# V2_aktuell_StdTeile_panel_small.net
KiCad netlist of a schematic drawn in EAGLE
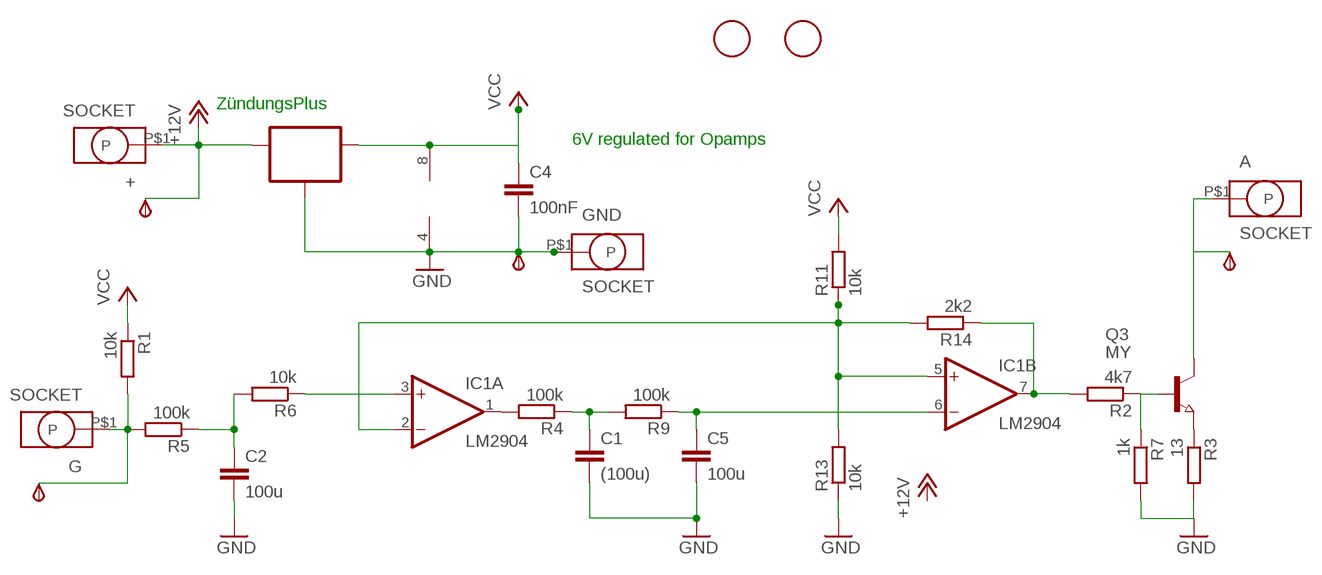
[diagram p0: schematic, sheet 1]
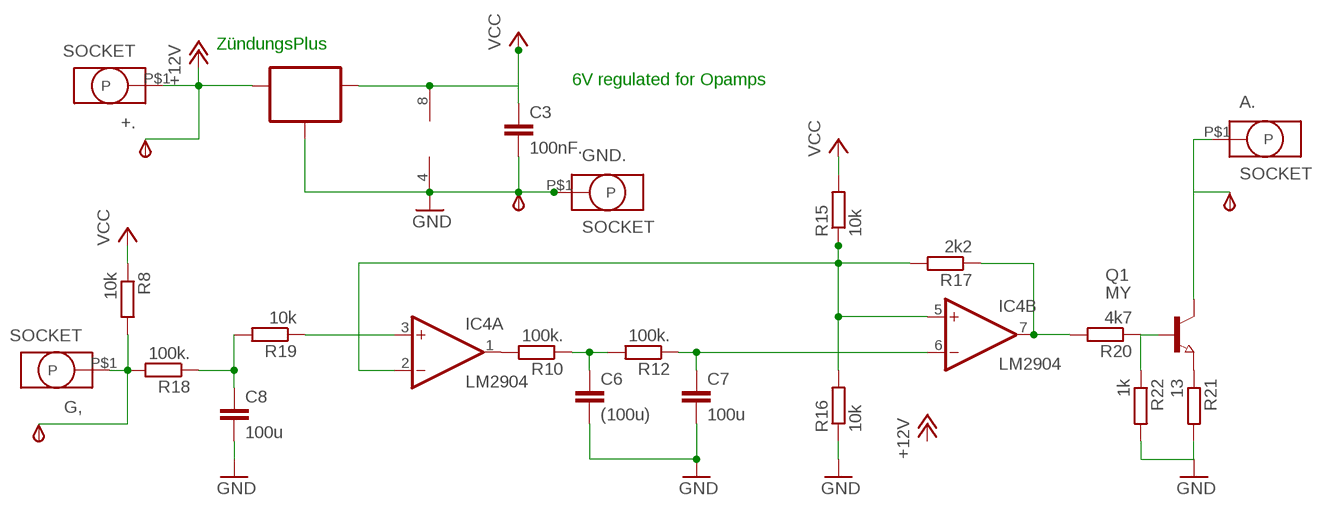
[diagram p1: schematic, sheet 2]

(export (version "E")
  (design (tool "Eeschema 10.0.6"))
  (components
    (comp (ref "+.")
      (value "SOCKET")
      (footprint "eagle-import:ID2.5MM")
      (libsource (lib "eagle-import") (part "SOCKET"))
    )
    (comp (ref "A.")
      (value "SOCKET")
      (footprint "eagle-import:ID2.5MM")
      (libsource (lib "eagle-import") (part "SOCKET"))
    )
    (comp (ref "C3")
      (value "100nF.")
      (footprint "eagle-import:C0805")
      (libsource (lib "eagle-import") (part "C-EUC0805"))
    )
    (comp (ref "C6")
      (value "(100u)")
      (footprint "eagle-import:C1206K")
      (libsource (lib "eagle-import") (part "C-EUC1206K"))
    )
    (comp (ref "C7")
      (value "100u")
      (footprint "eagle-import:C1206K")
      (libsource (lib "eagle-import") (part "C-EUC1206K"))
    )
    (comp (ref "C8")
      (value "100u")
      (footprint "eagle-import:C1206K")
      (libsource (lib "eagle-import") (part "C-EUC1206K"))
    )
    (comp (ref "G,")
      (value "SOCKET")
      (footprint "eagle-import:ID2.5MM")
      (libsource (lib "eagle-import") (part "SOCKET"))
    )
    (comp (ref "GND.")
      (value "SOCKET")
      (footprint "eagle-import:ID2.5MM")
      (libsource (lib "eagle-import") (part "SOCKET"))
    )
    (comp (ref "GND_1")
      (value "TPSB2.0")
      (footprint "eagle-import:B2.0")
      (libsource (lib "eagle-import") (part "TPSB2.0"))
    )
    (comp (ref "IC3")
      (value "78L06")
      (footprint "eagle-import:SOT89_ROUND")
      (libsource (lib "eagle-import") (part "78LXXSOT89_ROUND"))
    )
    (comp (ref "IC4")
      (value "LM2904")
      (footprint "eagle-import:SO08")
      (libsource (lib "eagle-import") (part "LM358D"))
    )
    (comp (ref "IN.")
      (value "TPSB2.0")
      (footprint "eagle-import:B2.0")
      (libsource (lib "eagle-import") (part "TPSB2.0"))
    )
    (comp (ref "OUT.")
      (value "TPSB2.0")
      (footprint "eagle-import:B2.0")
      (libsource (lib "eagle-import") (part "TPSB2.0"))
    )
    (comp (ref "Q1")
      (value "MY")
      (footprint "eagle-import:SOT89")
      (libsource (lib "eagle-import") (part "NPN-TRANSISTOR_SOT89"))
    )
    (comp (ref "R8")
      (value "10k")
      (footprint "eagle-import:R0805")
      (libsource (lib "eagle-import") (part "R-EU_R0805"))
    )
    (comp (ref "R10")
      (value "100k.")
      (footprint "eagle-import:R0805")
      (libsource (lib "eagle-import") (part "R-EU_R0805"))
    )
    (comp (ref "R12")
      (value "100k.")
      (footprint "eagle-import:R0805")
      (libsource (lib "eagle-import") (part "R-EU_R0805"))
    )
    (comp (ref "R15")
      (value "10k")
      (footprint "eagle-import:R0805")
      (libsource (lib "eagle-import") (part "R-EU_R0805"))
    )
    (comp (ref "R16")
      (value "10k")
      (footprint "eagle-import:R0805")
      (libsource (lib "eagle-import") (part "R-EU_R0805"))
    )
    (comp (ref "R17")
      (value "2k2")
      (footprint "eagle-import:R0805")
      (libsource (lib "eagle-import") (part "R-EU_R0805"))
    )
    (comp (ref "R18")
      (value "100k.")
      (footprint "eagle-import:R0805")
      (libsource (lib "eagle-import") (part "R-EU_R0805"))
    )
    (comp (ref "R19")
      (value "10k")
      (footprint "eagle-import:R0805")
      (libsource (lib "eagle-import") (part "R-EU_R0805"))
    )
    (comp (ref "R20")
      (value "4k7")
      (footprint "eagle-import:R0805")
      (libsource (lib "eagle-import") (part "R-EU_R0805"))
    )
    (comp (ref "R21")
      (value "13")
      (footprint "eagle-import:R1206")
      (libsource (lib "eagle-import") (part "R-EU_R1206"))
    )
    (comp (ref "R22")
      (value "1k")
      (footprint "eagle-import:R0805")
      (libsource (lib "eagle-import") (part "R-EU_R0805"))
    )
    (comp (ref "V+.")
      (value "TPSB2.0")
      (footprint "eagle-import:B2.0")
      (libsource (lib "eagle-import") (part "TPSB2.0"))
    )
    (comp (ref "+")
      (value "SOCKET")
      (footprint "eagle-import:ID2.5MM")
      (libsource (lib "eagle-import") (part "SOCKET"))
    )
    (comp (ref "A")
      (value "SOCKET")
      (footprint "eagle-import:ID2.5MM")
      (libsource (lib "eagle-import") (part "SOCKET"))
    )
    (comp (ref "C1")
      (value "(100u)")
      (footprint "eagle-import:C1206K")
      (libsource (lib "eagle-import") (part "C-EUC1206K"))
    )
    (comp (ref "C2")
      (value "100u")
      (footprint "eagle-import:C1206K")
      (libsource (lib "eagle-import") (part "C-EUC1206K"))
    )
    (comp (ref "C4")
      (value "100nF")
      (footprint "eagle-import:C0805")
      (libsource (lib "eagle-import") (part "C-EUC0805"))
    )
    (comp (ref "C5")
      (value "100u")
      (footprint "eagle-import:C1206K")
      (libsource (lib "eagle-import") (part "C-EUC1206K"))
    )
    (comp (ref "FID1")
      (value "FIDUCIALFIDUCIAL_1MM_WITH_SOLDERMASK")
      (footprint "eagle-import:FIDUCIAL_1MM_WITH_SOLDERMASK")
      (libsource (lib "eagle-import") (part "FIDUCIALFIDUCIAL_1MM_WITH_SOLDERMASK"))
    )
    (comp (ref "FID2")
      (value "FIDUCIALFIDUCIAL_1MM_WITH_SOLDERMASK")
      (footprint "eagle-import:FIDUCIAL_1MM_WITH_SOLDERMASK")
      (libsource (lib "eagle-import") (part "FIDUCIALFIDUCIAL_1MM_WITH_SOLDERMASK"))
    )
    (comp (ref "G")
      (value "SOCKET")
      (footprint "eagle-import:ID2.5MM")
      (libsource (lib "eagle-import") (part "SOCKET"))
    )
    (comp (ref "GND")
      (value "SOCKET")
      (footprint "eagle-import:ID2.5MM")
      (libsource (lib "eagle-import") (part "SOCKET"))
    )
    (comp (ref "GND_")
      (value "TPSB2.0")
      (footprint "eagle-import:B2.0")
      (libsource (lib "eagle-import") (part "TPSB2.0"))
    )
    (comp (ref "IC1")
      (value "LM2904")
      (footprint "eagle-import:SO08")
      (libsource (lib "eagle-import") (part "LM358D"))
    )
    (comp (ref "IC2")
      (value "78L06")
      (footprint "eagle-import:SOT89_ROUND")
      (libsource (lib "eagle-import") (part "78LXXSOT89_ROUND"))
    )
    (comp (ref "IN")
      (value "TPSB2.0")
      (footprint "eagle-import:B2.0")
      (libsource (lib "eagle-import") (part "TPSB2.0"))
    )
    (comp (ref "OUT")
      (value "TPSB2.0")
      (footprint "eagle-import:B2.0")
      (libsource (lib "eagle-import") (part "TPSB2.0"))
    )
    (comp (ref "Q3")
      (value "MY")
      (footprint "eagle-import:SOT89")
      (libsource (lib "eagle-import") (part "NPN-TRANSISTOR_SOT89"))
    )
    (comp (ref "R1")
      (value "10k")
      (footprint "eagle-import:R0805")
      (libsource (lib "eagle-import") (part "R-EU_R0805"))
    )
    (comp (ref "R2")
      (value "4k7")
      (footprint "eagle-import:R0805")
      (libsource (lib "eagle-import") (part "R-EU_R0805"))
    )
    (comp (ref "R3")
      (value "13")
      (footprint "eagle-import:R1206")
      (libsource (lib "eagle-import") (part "R-EU_R1206"))
    )
    (comp (ref "R4")
      (value "100k")
      (footprint "eagle-import:R0805")
      (libsource (lib "eagle-import") (part "R-EU_R0805"))
    )
    (comp (ref "R5")
      (value "100k")
      (footprint "eagle-import:R0805")
      (libsource (lib "eagle-import") (part "R-EU_R0805"))
    )
    (comp (ref "R6")
      (value "10k")
      (footprint "eagle-import:R0805")
      (libsource (lib "eagle-import") (part "R-EU_R0805"))
    )
    (comp (ref "R7")
      (value "1k")
      (footprint "eagle-import:R0805")
      (libsource (lib "eagle-import") (part "R-EU_R0805"))
    )
    (comp (ref "R9")
      (value "100k")
      (footprint "eagle-import:R0805")
      (libsource (lib "eagle-import") (part "R-EU_R0805"))
    )
    (comp (ref "R11")
      (value "10k")
      (footprint "eagle-import:R0805")
      (libsource (lib "eagle-import") (part "R-EU_R0805"))
    )
    (comp (ref "R13")
      (value "10k")
      (footprint "eagle-import:R0805")
      (libsource (lib "eagle-import") (part "R-EU_R0805"))
    )
    (comp (ref "R14")
      (value "2k2")
      (footprint "eagle-import:R0805")
      (libsource (lib "eagle-import") (part "R-EU_R0805"))
    )
    (comp (ref "V+")
      (value "TPSB2.0")
      (footprint "eagle-import:B2.0")
      (libsource (lib "eagle-import") (part "TPSB2.0"))
    )
  )
  (nets
    (net (code "1") (name "+12V") (class "Default")
      (node (ref "+") (pin "P$1") (pinfunction "P_P$1") (pintype "bidirectional"))
      (node (ref "+.") (pin "P$1") (pinfunction "P_P$1") (pintype "bidirectional"))
      (node (ref "IC2") (pin "3") (pinfunction "IN_3") (pintype "input"))
      (node (ref "IC3") (pin "3") (pinfunction "IN_3") (pintype "input"))
      (node (ref "V+") (pin "TP") (pinfunction "PP_TP") (pintype "input"))
      (node (ref "V+.") (pin "TP") (pinfunction "PP_TP") (pintype "input"))
    )
    (net (code "2") (name "GND") (class "Default")
      (node (ref "C1") (pin "2") (pinfunction "2_2") (pintype "passive"))
      (node (ref "C2") (pin "2") (pinfunction "2_2") (pintype "passive"))
      (node (ref "C3") (pin "2") (pinfunction "2_2") (pintype "passive"))
      (node (ref "C4") (pin "2") (pinfunction "2_2") (pintype "passive"))
      (node (ref "C5") (pin "2") (pinfunction "2_2") (pintype "passive"))
      (node (ref "C6") (pin "2") (pinfunction "2_2") (pintype "passive"))
      (node (ref "C7") (pin "2") (pinfunction "2_2") (pintype "passive"))
      (node (ref "C8") (pin "2") (pinfunction "2_2") (pintype "passive"))
      (node (ref "GND") (pin "P$1") (pinfunction "P_P$1") (pintype "bidirectional"))
      (node (ref "GND.") (pin "P$1") (pinfunction "P_P$1") (pintype "bidirectional"))
      (node (ref "GND_") (pin "TP") (pinfunction "PP_TP") (pintype "input"))
      (node (ref "GND_1") (pin "TP") (pinfunction "PP_TP") (pintype "input"))
      (node (ref "IC1") (pin "4") (pinfunction "V-_4") (pintype "power_in"))
      (node (ref "IC2") (pin "2") (pinfunction "GND_2") (pintype "input"))
      (node (ref "IC2") (pin "2@1") (pinfunction "GND_2@1") (pintype "input"))
      (node (ref "IC3") (pin "2") (pinfunction "GND_2") (pintype "input"))
      (node (ref "IC3") (pin "2@1") (pinfunction "GND_2@1") (pintype "input"))
      (node (ref "IC4") (pin "4") (pinfunction "V-_4") (pintype "power_in"))
      (node (ref "R13") (pin "1") (pinfunction "1_1") (pintype "passive"))
      (node (ref "R16") (pin "1") (pinfunction "1_1") (pintype "passive"))
      (node (ref "R21") (pin "2") (pinfunction "2_2") (pintype "passive"))
      (node (ref "R22") (pin "2") (pinfunction "2_2") (pintype "passive"))
      (node (ref "R3") (pin "2") (pinfunction "2_2") (pintype "passive"))
      (node (ref "R7") (pin "2") (pinfunction "2_2") (pintype "passive"))
    )
    (net (code "3") (name "Net-(A-P)") (class "Default")
      (node (ref "A") (pin "P$1") (pinfunction "P_P$1") (pintype "bidirectional"))
      (node (ref "OUT") (pin "TP") (pinfunction "PP_TP") (pintype "input"))
      (node (ref "Q3") (pin "2") (pinfunction "C_2") (pintype "passive"))
    )
    (net (code "4") (name "Net-(A.-P)") (class "Default")
      (node (ref "A.") (pin "P$1") (pinfunction "P_P$1") (pintype "bidirectional"))
      (node (ref "OUT.") (pin "TP") (pinfunction "PP_TP") (pintype "input"))
      (node (ref "Q1") (pin "2") (pinfunction "C_2") (pintype "passive"))
    )
    (net (code "5") (name "Net-(C1-Pad1)") (class "Default")
      (node (ref "C1") (pin "1") (pinfunction "1_1") (pintype "passive"))
      (node (ref "R4") (pin "1") (pinfunction "1_1") (pintype "passive"))
      (node (ref "R9") (pin "2") (pinfunction "2_2") (pintype "passive"))
    )
    (net (code "6") (name "Net-(C2-Pad1)") (class "Default")
      (node (ref "C2") (pin "1") (pinfunction "1_1") (pintype "passive"))
      (node (ref "R5") (pin "1") (pinfunction "1_1") (pintype "passive"))
      (node (ref "R6") (pin "2") (pinfunction "2_2") (pintype "passive"))
    )
    (net (code "7") (name "Net-(C6-Pad1)") (class "Default")
      (node (ref "C6") (pin "1") (pinfunction "1_1") (pintype "passive"))
      (node (ref "R10") (pin "1") (pinfunction "1_1") (pintype "passive"))
      (node (ref "R12") (pin "2") (pinfunction "2_2") (pintype "passive"))
    )
    (net (code "8") (name "Net-(C8-Pad1)") (class "Default")
      (node (ref "C8") (pin "1") (pinfunction "1_1") (pintype "passive"))
      (node (ref "R18") (pin "1") (pinfunction "1_1") (pintype "passive"))
      (node (ref "R19") (pin "2") (pinfunction "2_2") (pintype "passive"))
    )
    (net (code "9") (name "Net-(G,-P)") (class "Default")
      (node (ref "G,") (pin "P$1") (pinfunction "P_P$1") (pintype "bidirectional"))
      (node (ref "IN.") (pin "TP") (pinfunction "PP_TP") (pintype "input"))
      (node (ref "R18") (pin "2") (pinfunction "2_2") (pintype "passive"))
      (node (ref "R8") (pin "2") (pinfunction "2_2") (pintype "passive"))
    )
    (net (code "10") (name "Net-(G-P)") (class "Default")
      (node (ref "G") (pin "P$1") (pinfunction "P_P$1") (pintype "bidirectional"))
      (node (ref "IN") (pin "TP") (pinfunction "PP_TP") (pintype "input"))
      (node (ref "R1") (pin "2") (pinfunction "2_2") (pintype "passive"))
      (node (ref "R5") (pin "2") (pinfunction "2_2") (pintype "passive"))
    )
    (net (code "11") (name "Net-(IC1A-+IN)") (class "Default")
      (node (ref "IC1") (pin "3") (pinfunction "+IN_3") (pintype "input"))
      (node (ref "R6") (pin "1") (pinfunction "1_1") (pintype "passive"))
    )
    (net (code "12") (name "Net-(IC1A--IN)") (class "Default")
      (node (ref "IC1") (pin "2") (pinfunction "-IN_2") (pintype "input"))
      (node (ref "IC1") (pin "5") (pinfunction "+IN_5") (pintype "input"))
      (node (ref "R11") (pin "1") (pinfunction "1_1") (pintype "passive"))
      (node (ref "R13") (pin "2") (pinfunction "2_2") (pintype "passive"))
      (node (ref "R14") (pin "2") (pinfunction "2_2") (pintype "passive"))
    )
    (net (code "13") (name "Net-(IC1A-OUT)") (class "Default")
      (node (ref "IC1") (pin "1") (pinfunction "OUT_1") (pintype "output"))
      (node (ref "R4") (pin "2") (pinfunction "2_2") (pintype "passive"))
    )
    (net (code "14") (name "Net-(IC1B--IN)") (class "Default")
      (node (ref "C5") (pin "1") (pinfunction "1_1") (pintype "passive"))
      (node (ref "IC1") (pin "6") (pinfunction "-IN_6") (pintype "input"))
      (node (ref "R9") (pin "1") (pinfunction "1_1") (pintype "passive"))
    )
    (net (code "15") (name "Net-(IC1B-OUT)") (class "Default")
      (node (ref "IC1") (pin "7") (pinfunction "OUT_7") (pintype "output"))
      (node (ref "R14") (pin "1") (pinfunction "1_1") (pintype "passive"))
      (node (ref "R2") (pin "2") (pinfunction "2_2") (pintype "passive"))
    )
    (net (code "16") (name "Net-(IC4A-+IN)") (class "Default")
      (node (ref "IC4") (pin "3") (pinfunction "+IN_3") (pintype "input"))
      (node (ref "R19") (pin "1") (pinfunction "1_1") (pintype "passive"))
    )
    (net (code "17") (name "Net-(IC4A--IN)") (class "Default")
      (node (ref "IC4") (pin "2") (pinfunction "-IN_2") (pintype "input"))
      (node (ref "IC4") (pin "5") (pinfunction "+IN_5") (pintype "input"))
      (node (ref "R15") (pin "1") (pinfunction "1_1") (pintype "passive"))
      (node (ref "R16") (pin "2") (pinfunction "2_2") (pintype "passive"))
      (node (ref "R17") (pin "2") (pinfunction "2_2") (pintype "passive"))
    )
    (net (code "18") (name "Net-(IC4A-OUT)") (class "Default")
      (node (ref "IC4") (pin "1") (pinfunction "OUT_1") (pintype "output"))
      (node (ref "R10") (pin "2") (pinfunction "2_2") (pintype "passive"))
    )
    (net (code "19") (name "Net-(IC4B--IN)") (class "Default")
      (node (ref "C7") (pin "1") (pinfunction "1_1") (pintype "passive"))
      (node (ref "IC4") (pin "6") (pinfunction "-IN_6") (pintype "input"))
      (node (ref "R12") (pin "1") (pinfunction "1_1") (pintype "passive"))
    )
    (net (code "20") (name "Net-(IC4B-OUT)") (class "Default")
      (node (ref "IC4") (pin "7") (pinfunction "OUT_7") (pintype "output"))
      (node (ref "R17") (pin "1") (pinfunction "1_1") (pintype "passive"))
      (node (ref "R20") (pin "2") (pinfunction "2_2") (pintype "passive"))
    )
    (net (code "21") (name "Net-(Q1-B)") (class "Default")
      (node (ref "Q1") (pin "1") (pinfunction "B_1") (pintype "passive"))
      (node (ref "R20") (pin "1") (pinfunction "1_1") (pintype "passive"))
      (node (ref "R22") (pin "1") (pinfunction "1_1") (pintype "passive"))
    )
    (net (code "22") (name "Net-(Q1-E)") (class "Default")
      (node (ref "Q1") (pin "3") (pinfunction "E_3") (pintype "passive"))
      (node (ref "R21") (pin "1") (pinfunction "1_1") (pintype "passive"))
    )
    (net (code "23") (name "Net-(Q3-B)") (class "Default")
      (node (ref "Q3") (pin "1") (pinfunction "B_1") (pintype "passive"))
      (node (ref "R2") (pin "1") (pinfunction "1_1") (pintype "passive"))
      (node (ref "R7") (pin "1") (pinfunction "1_1") (pintype "passive"))
    )
    (net (code "24") (name "Net-(Q3-E)") (class "Default")
      (node (ref "Q3") (pin "3") (pinfunction "E_3") (pintype "passive"))
      (node (ref "R3") (pin "1") (pinfunction "1_1") (pintype "passive"))
    )
    (net (code "25") (name "VCC") (class "Default")
      (node (ref "C3") (pin "1") (pinfunction "1_1") (pintype "passive"))
      (node (ref "C4") (pin "1") (pinfunction "1_1") (pintype "passive"))
      (node (ref "IC1") (pin "8") (pinfunction "V+_8") (pintype "power_in"))
      (node (ref "IC2") (pin "1") (pinfunction "OUT_1") (pintype "passive"))
      (node (ref "IC3") (pin "1") (pinfunction "OUT_1") (pintype "passive"))
      (node (ref "IC4") (pin "8") (pinfunction "V+_8") (pintype "power_in"))
      (node (ref "R1") (pin "1") (pinfunction "1_1") (pintype "passive"))
      (node (ref "R11") (pin "2") (pinfunction "2_2") (pintype "passive"))
      (node (ref "R15") (pin "2") (pinfunction "2_2") (pintype "passive"))
      (node (ref "R8") (pin "1") (pinfunction "1_1") (pintype "passive"))
    )
  )
)
